# main.net
KiCad netlist of a schematic drawn in EAGLE
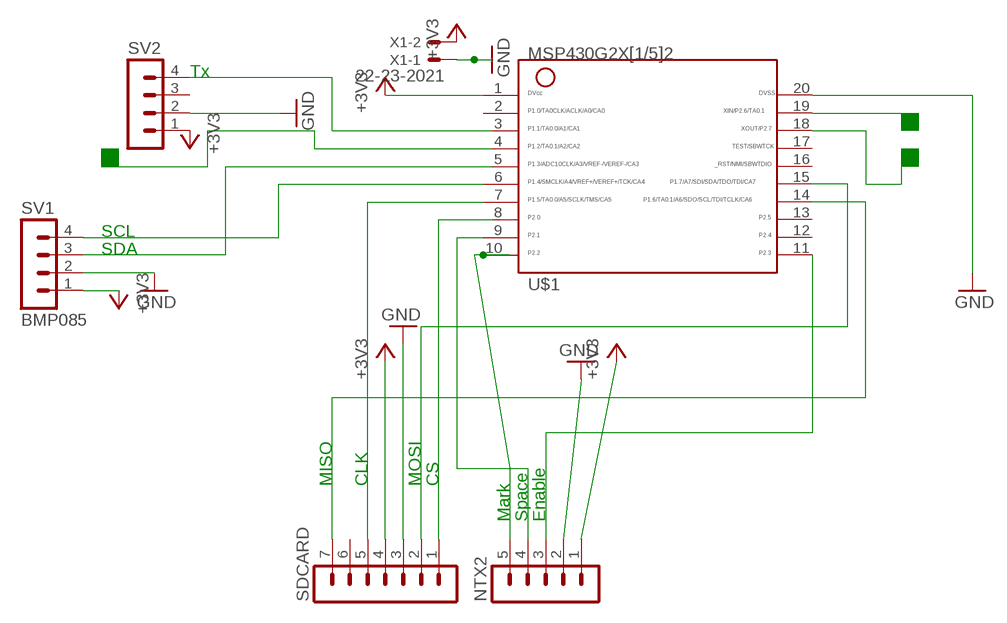
[diagram p0: schematic, sheet 1]

(export (version "E")
  (design (tool "Eeschema 10.0.6"))
  (components
    (comp (ref "NTX2")
      (value "MA05-1")
      (footprint "eagle-import:MA05-1")
      (libsource (lib "eagle-import") (part "MA05-1"))
    )
    (comp (ref "SDCARD")
      (value "MA07-1")
      (footprint "eagle-import:MA07-1")
      (libsource (lib "eagle-import") (part "MA07-1"))
    )
    (comp (ref "SV1")
      (value "BMP085")
      (footprint "eagle-import:MA04-1")
      (libsource (lib "eagle-import") (part "MA04-1"))
    )
    (comp (ref "SV2")
      (value "MA04-1")
      (footprint "eagle-import:MA04-1")
      (libsource (lib "eagle-import") (part "MA04-1"))
    )
    (comp (ref "U$1")
      (value "G2X[1/5]2---N20")
      (footprint "eagle-import:N20")
      (libsource (lib "eagle-import") (part "G2X[1/5]2---N20"))
    )
    (comp (ref "X1")
      (value "22-23-2021")
      (footprint "eagle-import:22-23-2021")
      (fields (field (name "MF") "MOLEX"))
      (libsource (lib "eagle-import") (part "22-23-2021"))
    )
  )
  (nets
    (net (code "1") (name "+3V3") (class "Default")
      (node (ref "NTX2") (pin "1") (pinfunction "1_1") (pintype "passive"))
      (node (ref "SDCARD") (pin "4") (pinfunction "4_4") (pintype "passive"))
      (node (ref "SV1") (pin "1") (pinfunction "1_1") (pintype "passive"))
      (node (ref "SV2") (pin "1") (pinfunction "1_1") (pintype "passive"))
      (node (ref "U$1") (pin "1") (pinfunction "1_1") (pintype "bidirectional"))
      (node (ref "X1") (pin "2") (pinfunction "S_2") (pintype "passive"))
    )
    (net (code "2") (name "GND") (class "Default")
      (node (ref "NTX2") (pin "2") (pinfunction "2_2") (pintype "passive"))
      (node (ref "SDCARD") (pin "3") (pinfunction "3_3") (pintype "passive"))
      (node (ref "SV1") (pin "2") (pinfunction "2_2") (pintype "passive"))
      (node (ref "SV2") (pin "2") (pinfunction "2_2") (pintype "passive"))
      (node (ref "U$1") (pin "20") (pinfunction "20_20") (pintype "bidirectional"))
      (node (ref "X1") (pin "1") (pinfunction "S_1") (pintype "passive"))
    )
    (net (code "3") (name "Net-(NTX2-Pad3)") (class "Default")
      (node (ref "NTX2") (pin "3") (pinfunction "3_3") (pintype "passive"))
      (node (ref "U$1") (pin "11") (pinfunction "11_11") (pintype "bidirectional"))
    )
    (net (code "4") (name "Net-(NTX2-Pad4)") (class "Default")
      (node (ref "NTX2") (pin "4") (pinfunction "4_4") (pintype "passive"))
      (node (ref "U$1") (pin "9") (pinfunction "9_9") (pintype "bidirectional"))
    )
    (net (code "5") (name "Net-(NTX2-Pad5)") (class "Default")
      (node (ref "NTX2") (pin "5") (pinfunction "5_5") (pintype "passive"))
      (node (ref "U$1") (pin "10") (pinfunction "10_10") (pintype "bidirectional"))
    )
    (net (code "6") (name "Net-(SDCARD-Pad1)") (class "Default")
      (node (ref "SDCARD") (pin "1") (pinfunction "1_1") (pintype "passive"))
      (node (ref "U$1") (pin "8") (pinfunction "8_8") (pintype "bidirectional"))
    )
    (net (code "7") (name "Net-(SDCARD-Pad2)") (class "Default")
      (node (ref "SDCARD") (pin "2") (pinfunction "2_2") (pintype "passive"))
      (node (ref "U$1") (pin "15") (pinfunction "15_15") (pintype "bidirectional"))
    )
    (net (code "8") (name "Net-(SDCARD-Pad5)") (class "Default")
      (node (ref "SDCARD") (pin "5") (pinfunction "5_5") (pintype "passive"))
      (node (ref "U$1") (pin "7") (pinfunction "7_7") (pintype "bidirectional"))
    )
    (net (code "9") (name "Net-(SDCARD-Pad7)") (class "Default")
      (node (ref "SDCARD") (pin "7") (pinfunction "7_7") (pintype "passive"))
      (node (ref "U$1") (pin "14") (pinfunction "14_14") (pintype "bidirectional"))
    )
    (net (code "10") (name "Net-(SV1-Pad3)") (class "Default")
      (node (ref "SV1") (pin "3") (pinfunction "3_3") (pintype "passive"))
      (node (ref "U$1") (pin "5") (pinfunction "5_5") (pintype "bidirectional"))
    )
    (net (code "11") (name "Net-(SV1-Pad4)") (class "Default")
      (node (ref "SV1") (pin "4") (pinfunction "4_4") (pintype "passive"))
      (node (ref "U$1") (pin "6") (pinfunction "6_6") (pintype "bidirectional"))
    )
    (net (code "12") (name "Net-(SV2-Pad4)") (class "Default")
      (node (ref "SV2") (pin "4") (pinfunction "4_4") (pintype "passive"))
      (node (ref "U$1") (pin "3") (pinfunction "3_3") (pintype "bidirectional"))
    )
    (net (code "13") (name "unconnected-(SDCARD-Pad6)") (class "Default")
      (node (ref "SDCARD") (pin "6") (pinfunction "6_6") (pintype "passive"))
    )
    (net (code "14") (name "unconnected-(SV2-Pad3)") (class "Default")
      (node (ref "SV2") (pin "3") (pinfunction "3_3") (pintype "passive"))
    )
    (net (code "15") (name "unconnected-(U$1-Pad2)") (class "Default")
      (node (ref "U$1") (pin "2") (pinfunction "2_2") (pintype "bidirectional"))
    )
    (net (code "16") (name "unconnected-(U$1-Pad4)") (class "Default")
      (node (ref "U$1") (pin "4") (pinfunction "4_4") (pintype "bidirectional"))
    )
    (net (code "17") (name "unconnected-(U$1-Pad12)") (class "Default")
      (node (ref "U$1") (pin "12") (pinfunction "12_12") (pintype "bidirectional"))
    )
    (net (code "18") (name "unconnected-(U$1-Pad13)") (class "Default")
      (node (ref "U$1") (pin "13") (pinfunction "13_13") (pintype "bidirectional"))
    )
    (net (code "19") (name "unconnected-(U$1-Pad16)") (class "Default")
      (node (ref "U$1") (pin "16") (pinfunction "16_16") (pintype "bidirectional"))
    )
    (net (code "20") (name "unconnected-(U$1-Pad17)") (class "Default")
      (node (ref "U$1") (pin "17") (pinfunction "17_17") (pintype "bidirectional"))
    )
    (net (code "21") (name "unconnected-(U$1-Pad18)") (class "Default")
      (node (ref "U$1") (pin "18") (pinfunction "18_18") (pintype "bidirectional"))
    )
    (net (code "22") (name "unconnected-(U$1-Pad19)") (class "Default")
      (node (ref "U$1") (pin "19") (pinfunction "19_19") (pintype "bidirectional"))
    )
  )
)
